# AMU-S10-V00-Buzzer.net
KiCad netlist of a schematic drawn in Altium Designer
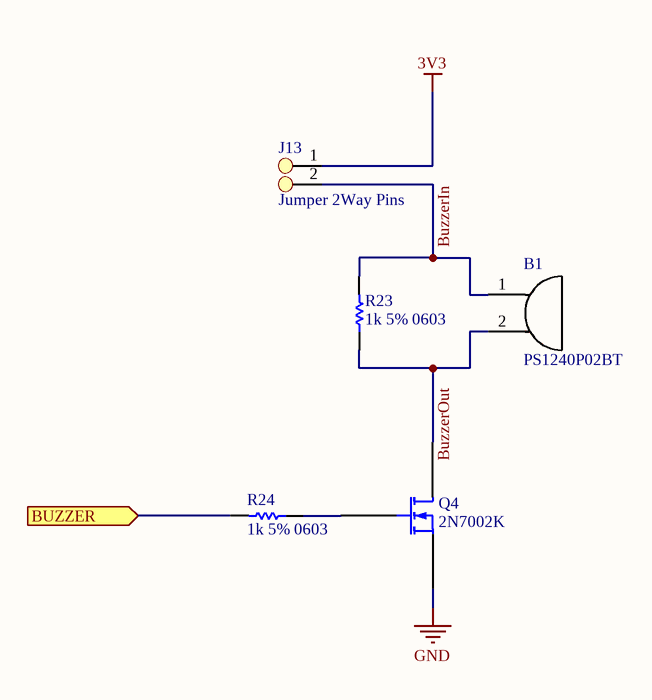
[diagram p0: AMU-S10-V00-Buzzer.SchDoc]

(export (version "E")
  (design (tool "Eeschema 10.0.6"))
  (components
    (comp (ref "B1")
      (value "PS1240P02BT")
      (footprint "PS1240P02BT")
      (description "Buzzers Transducer, Externally Driven Piezo 3V 4kHz 60dB @ 3V, 10cm Through Hole PC Pins")
      (libsource (lib "QUTMS_BuzzerLibrary") (part "PS1240P02BT"))
    )
    (comp (ref "J13")
      (value "Jumper 2Way Pins")
      (footprint "Jumper_2Way_Pin")
      (description "Jumper 2Way Side Pins")
      (libsource (lib "QUTMS_JumperLibrary") (part "Jumper 2Way Side Pins"))
    )
    (comp (ref "Q4")
      (value "2N7002K")
      (footprint "SOT-23-3")
      (description "N-Channel 60V 300mA (Ta) 350mW (Ta) Surface Mount SOT-23 (TO-236AB)")
      (libsource (lib "QUTMS_Transistors") (part "2N7002K"))
    )
    (comp (ref "R23")
      (value "1k 5% 0603")
      (footprint "Res_ThinFilm_0603")
      (description "Resistor, SMD, 1k, 0.1W, 5%, 0603")
      (libsource (lib "StandardResistors") (part "1k 5% 0603"))
    )
    (comp (ref "R24")
      (value "1k 5% 0603")
      (footprint "Res_ThinFilm_0603")
      (description "Resistor, SMD, 1k, 0.1W, 5%, 0603")
      (libsource (lib "StandardResistors") (part "1k 5% 0603"))
    )
  )
  (nets
    (net (code "1") (name "/BUZZER") (class "Default")
      (node (ref "R24") (pin "2") (pinfunction "2_2") (pintype "passive"))
    )
    (net (code "2") (name "/BuzzerIn") (class "Default")
      (node (ref "B1") (pin "1") (pinfunction "1_1") (pintype "passive"))
      (node (ref "J13") (pin "2") (pinfunction "2_2") (pintype "passive"))
      (node (ref "R23") (pin "2") (pinfunction "2_2") (pintype "passive"))
    )
    (net (code "3") (name "/BuzzerOut") (class "Default")
      (node (ref "B1") (pin "2") (pinfunction "2_2") (pintype "passive"))
      (node (ref "Q4") (pin "D") (pinfunction "D_D") (pintype "passive"))
      (node (ref "R23") (pin "1") (pinfunction "1_1") (pintype "passive"))
    )
    (net (code "4") (name "3V3") (class "Default")
      (node (ref "J13") (pin "1") (pinfunction "1_1") (pintype "passive"))
    )
    (net (code "5") (name "GND") (class "Default")
      (node (ref "Q4") (pin "S") (pinfunction "S_S") (pintype "passive"))
    )
    (net (code "6") (name "Net-(Q4-PadG)") (class "Default")
      (node (ref "Q4") (pin "G") (pinfunction "G_G") (pintype "passive"))
      (node (ref "R24") (pin "1") (pinfunction "1_1") (pintype "passive"))
    )
  )
)
